# SAMW25_Xplained_Pro_Connectors.net
KiCad netlist of a schematic drawn in Altium Designer
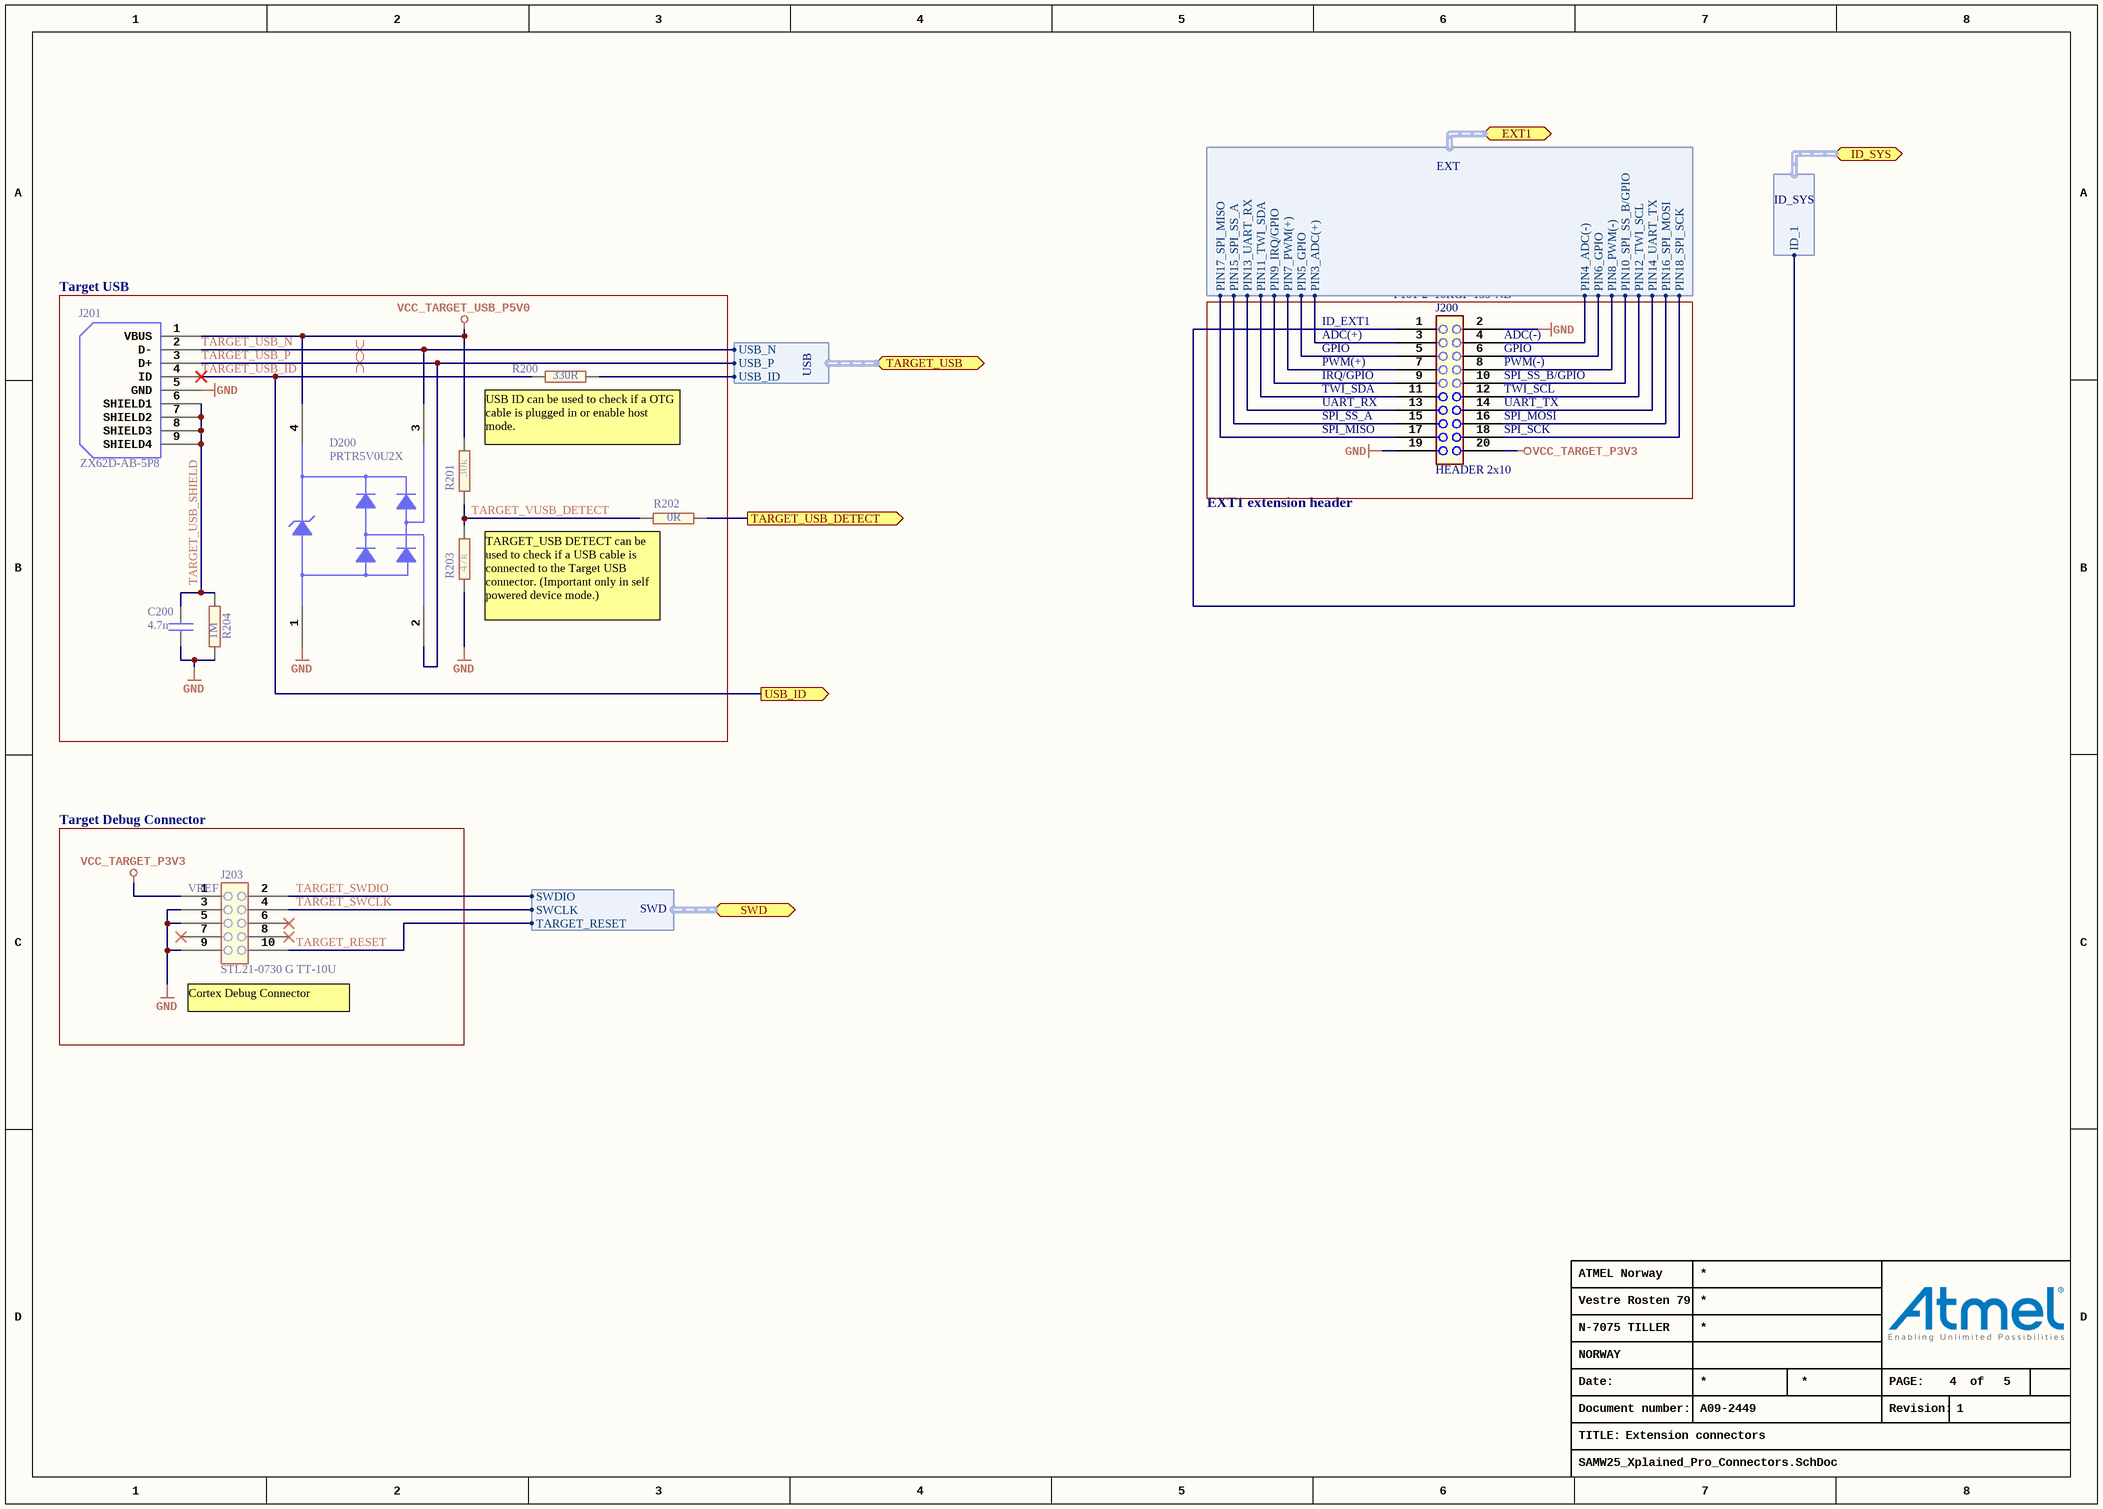
[diagram p0: SAMW25_Xplained_Pro_Connectors.SchDoc]

(export (version "E")
  (design (tool "Eeschema 10.0.6"))
  (components
    (comp (ref "C200")
      (value "4.7n")
      (footprint "AP1-00053")
      (description "Ceramic capacitor, SMD 0402, X7R, 25V, +/-10%")
      (fields
        (field (name "TOLERANCE") "25V, +/-10%")
        (field (name "Comment") "CAP-NONPOL")
        (field (name "VERIFIED BY") "Lars Helge Mo")
      )
      (libsource (lib "AltiumDbLib") (part "CAP-NONPOL"))
    )
    (comp (ref "D200")
      (value "PRTR5V0U2X")
      (footprint "AP4-00001")
      (description "Double rail-to-rail USB ESD protection diode")
      (fields (field (name "MANUFACTURER") "Philips") (field (name "VERIFIED BY") "Lars Nordin"))
      (libsource (lib "AltiumDbLib") (part "PRTR5V0U2X"))
    )
    (comp (ref "J200")
      (value "HEADER 2x10")
      (footprint "AP8-00622")
      (description "Pin header, 2x10, Right Angle, 2.54mm, THM, Pin In Paste")
      (fields
        (field (name "ALTIUM_VALUE") "P101-2*10RGF-139-ND")
        (field (name "MPN") "P101-2*10RGF-139-ND")
        (field (name "VERIFIED BY") "Lars Helge Mo")
      )
      (libsource (lib "AltiumDbLib") (part "HEADER 2x10"))
    )
    (comp (ref "J201")
      (value "ZX62D-AB-5P8")
      (footprint "AP8-00852")
      (description "Micro USB AB Connector, Standard SMT + DIP")
      (fields (field (name "Comment") "2,000 pieces per reel") (field (name "VERIFIED BY") "Eirik Rasmussen"))
      (libsource (lib "AltiumDbLib") (part "USB_AB"))
    )
    (comp (ref "J203")
      (value "HEADER 2x5")
      (footprint "AP8-00257")
      (description "2x5 pin header, 1.27mm pitch, THM")
      (fields
        (field (name "MANUFACTURER") "Garry")
        (field (name "MPN") "STL21-0730 G TT-10U")
        (field (name "VERIFIED BY") "Lars Helge Mo")
      )
      (libsource (lib "AltiumDbLib") (part "HEADER 2x5"))
    )
    (comp (ref "R200")
      (value "330R")
      (footprint "AP2-00000")
      (description "Thick film resistor, SMD 0402, 1/16W, 1%")
      (fields
        (field (name "TOLERANCE") "1 %")
        (field (name "Comment") "R2")
        (field (name "VERIFIED BY") "Lars Helge Mo")
      )
      (libsource (lib "AltiumDbLib") (part "R2"))
    )
    (comp (ref "R201")
      (value "30k")
      (footprint "AP2-00011")
      (description "Thick film resistor, SMD 0402, 1/16W, 1%")
      (fields
        (field (name "TOLERANCE") "1 %")
        (field (name "Comment") "R2")
        (field (name "VERIFIED BY") "Lars Helge Mo")
      )
      (libsource (lib "") (part "R2_3"))
    )
    (comp (ref "R202")
      (value "0R")
      (footprint "AP2-00000")
      (description "RES 0.0 OHM 1/16W 0402 SMD")
      (fields
        (field (name "TOLERANCE") "1 %")
        (field (name "MPN") "RMCF0402ZT0R00")
        (field (name "VERIFIED BY") "Lars Helge Mo")
      )
      (libsource (lib "AltiumDbLib") (part "R2"))
    )
    (comp (ref "R203")
      (value "47k")
      (footprint "AP2-00011")
      (description "Thick film resistor, SMD 0402, 1/16W, 1%")
      (fields
        (field (name "TOLERANCE") "1 %")
        (field (name "Comment") "R2")
        (field (name "VERIFIED BY") "Lars Helge Mo")
      )
      (libsource (lib "") (part "R2_2"))
    )
    (comp (ref "R204")
      (value "1M")
      (footprint "AP2-00011")
      (description "Thick film resistor, SMD 0402, 1/16W, 1%")
      (fields
        (field (name "TOLERANCE") "1 %")
        (field (name "MANUFACTURER") "KOA")
        (field (name "VERIFIED BY") "Lars Helge Mo")
      )
      (libsource (lib "") (part "R2_1"))
    )
  )
  (nets
    (net (code "4") (name "/ID_1") (class "Default")
      (node (ref "J200") (pin "1") (pinfunction "1_1") (pintype "passive"))
    )
    (net (code "5") (name "/PIN3_ADC(+)") (class "Default")
      (node (ref "J200") (pin "3") (pinfunction "3_3") (pintype "passive"))
    )
    (net (code "6") (name "/PIN4_ADC(-)") (class "Default")
      (node (ref "J200") (pin "4") (pinfunction "4_4") (pintype "passive"))
    )
    (net (code "7") (name "/PIN5_GPIO") (class "Default")
      (node (ref "J200") (pin "5") (pinfunction "5_5") (pintype "passive"))
    )
    (net (code "8") (name "/PIN6_GPIO") (class "Default")
      (node (ref "J200") (pin "6") (pinfunction "6_6") (pintype "passive"))
    )
    (net (code "9") (name "/PIN7_PWM(+)") (class "Default")
      (node (ref "J200") (pin "7") (pinfunction "7_7") (pintype "passive"))
    )
    (net (code "10") (name "/PIN8_PWM(-)") (class "Default")
      (node (ref "J200") (pin "8") (pinfunction "8_8") (pintype "passive"))
    )
    (net (code "11") (name "/PIN9_IRQ{slash}GPIO") (class "Default")
      (node (ref "J200") (pin "9") (pinfunction "9_9") (pintype "passive"))
    )
    (net (code "12") (name "/PIN10_SPI_SS_B{slash}GPIO") (class "Default")
      (node (ref "J200") (pin "10") (pinfunction "10_10") (pintype "passive"))
    )
    (net (code "13") (name "/PIN11_TWI_SDA") (class "Default")
      (node (ref "J200") (pin "11") (pinfunction "11_11") (pintype "passive"))
    )
    (net (code "14") (name "/PIN12_TWI_SCL") (class "Default")
      (node (ref "J200") (pin "12") (pinfunction "12_12") (pintype "passive"))
    )
    (net (code "15") (name "/PIN13_UART_RX") (class "Default")
      (node (ref "J200") (pin "13") (pinfunction "13_13") (pintype "passive"))
    )
    (net (code "16") (name "/PIN14_UART_TX") (class "Default")
      (node (ref "J200") (pin "14") (pinfunction "14_14") (pintype "passive"))
    )
    (net (code "17") (name "/PIN15_SPI_SS_A") (class "Default")
      (node (ref "J200") (pin "15") (pinfunction "15_15") (pintype "passive"))
    )
    (net (code "18") (name "/PIN16_SPI_MOSI") (class "Default")
      (node (ref "J200") (pin "16") (pinfunction "16_16") (pintype "passive"))
    )
    (net (code "19") (name "/PIN17_SPI_MISO") (class "Default")
      (node (ref "J200") (pin "17") (pinfunction "17_17") (pintype "passive"))
    )
    (net (code "20") (name "/PIN18_SPI_SCK") (class "Default")
      (node (ref "J200") (pin "18") (pinfunction "18_18") (pintype "passive"))
    )
    (net (code "21") (name "/TARGET_RESET") (class "Default")
      (node (ref "J203") (pin "10") (pinfunction "10_10") (pintype "passive"))
    )
    (net (code "22") (name "/TARGET_SWCLK") (class "Default")
      (node (ref "J203") (pin "4") (pinfunction "4_4") (pintype "passive"))
    )
    (net (code "23") (name "/TARGET_SWDIO") (class "Default")
      (node (ref "J203") (pin "2") (pinfunction "2_2") (pintype "passive"))
    )
    (net (code "24") (name "/TARGET_USB_DETECT") (class "Default")
      (node (ref "R202") (pin "2") (pinfunction "2_2") (pintype "passive"))
    )
    (net (code "25") (name "/TARGET_USB_ID") (class "Default")
      (node (ref "J201") (pin "4") (pinfunction "ID_4") (pintype "passive"))
      (node (ref "R200") (pin "1") (pinfunction "1_1") (pintype "passive"))
    )
    (net (code "26") (name "/TARGET_USB_N") (class "Default")
      (node (ref "D200") (pin "3") (pinfunction "I/O_2_3") (pintype "passive"))
      (node (ref "J201") (pin "2") (pinfunction "D-_2") (pintype "passive"))
    )
    (net (code "27") (name "/TARGET_USB_P") (class "Default")
      (node (ref "D200") (pin "2") (pinfunction "I/O_1_2") (pintype "passive"))
      (node (ref "J201") (pin "3") (pinfunction "D+_3") (pintype "passive"))
    )
    (net (code "28") (name "/TARGET_USB_SHIELD") (class "Default")
      (node (ref "C200") (pin "2") (pinfunction "2_2") (pintype "passive"))
      (node (ref "J201") (pin "6") (pinfunction "SHIELD1_6") (pintype "passive"))
      (node (ref "J201") (pin "7") (pinfunction "SHIELD2_7") (pintype "passive"))
      (node (ref "J201") (pin "8") (pinfunction "SHIELD3_8") (pintype "passive"))
      (node (ref "J201") (pin "9") (pinfunction "SHIELD4_9") (pintype "passive"))
      (node (ref "R204") (pin "2") (pinfunction "2_2") (pintype "passive"))
    )
    (net (code "29") (name "/TARGET_VUSB_DETECT") (class "Default")
      (node (ref "R201") (pin "1") (pinfunction "1_1") (pintype "passive"))
      (node (ref "R202") (pin "1") (pinfunction "1_1") (pintype "passive"))
      (node (ref "R203") (pin "2") (pinfunction "2_2") (pintype "passive"))
    )
    (net (code "33") (name "GND") (class "Default")
      (node (ref "C200") (pin "1") (pinfunction "1_1") (pintype "passive"))
      (node (ref "D200") (pin "1") (pinfunction "GND_1") (pintype "passive"))
      (node (ref "J200") (pin "19") (pinfunction "19_19") (pintype "passive"))
      (node (ref "J200") (pin "2") (pinfunction "2_2") (pintype "passive"))
      (node (ref "J201") (pin "5") (pinfunction "GND_5") (pintype "passive"))
      (node (ref "J203") (pin "3") (pinfunction "3_3") (pintype "passive"))
      (node (ref "J203") (pin "5") (pinfunction "5_5") (pintype "passive"))
      (node (ref "J203") (pin "9") (pinfunction "9_9") (pintype "passive"))
      (node (ref "R203") (pin "1") (pinfunction "1_1") (pintype "passive"))
      (node (ref "R204") (pin "1") (pinfunction "1_1") (pintype "passive"))
    )
    (net (code "34") (name "VCC_TARGET_P3V3") (class "Default")
      (node (ref "J200") (pin "20") (pinfunction "20_20") (pintype "passive"))
      (node (ref "J203") (pin "1") (pinfunction "1_1") (pintype "passive"))
    )
    (net (code "35") (name "VCC_TARGET_USB_P5V0") (class "Default")
      (node (ref "D200") (pin "4") (pinfunction "VCC_4") (pintype "passive"))
      (node (ref "J201") (pin "1") (pinfunction "VBUS_1") (pintype "passive"))
      (node (ref "R201") (pin "2") (pinfunction "2_2") (pintype "passive"))
    )
    (net (code "36") (name "unconnected-(J203-Pad6)") (class "Default")
      (node (ref "J203") (pin "6") (pinfunction "6_6") (pintype "passive+no_connect"))
    )
    (net (code "37") (name "unconnected-(J203-Pad7)") (class "Default")
      (node (ref "J203") (pin "7") (pinfunction "7_7") (pintype "passive+no_connect"))
    )
    (net (code "38") (name "unconnected-(J203-Pad8)") (class "Default")
      (node (ref "J203") (pin "8") (pinfunction "8_8") (pintype "passive+no_connect"))
    )
    (net (code "39") (name "unconnected-(R200-Pad2)") (class "Default")
      (node (ref "R200") (pin "2") (pinfunction "2_2") (pintype "passive"))
    )
  )
)
